# rs232_part.net
KiCad netlist of a schematic drawn in Altium Designer
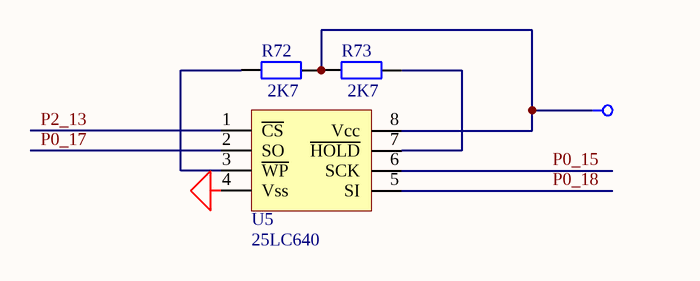
[diagram p0: rs232_part.SchDoc]

(export (version "E")
  (design (tool "Eeschema 10.0.6"))
  (components
    (comp (ref "R72")
      (value "2K7")
      (footprint "_1206")
      (description "Resistor")
      (fields (field (name "MANUFACTURER") "Generic Components") (field (name "PUBLISHER") "Altium Limited"))
      (libsource (lib "Miscellaneous Devices") (part "Res2"))
    )
    (comp (ref "R73")
      (value "2K7")
      (footprint "_1206")
      (description "Resistor")
      (fields (field (name "MANUFACTURER") "Generic Components") (field (name "PUBLISHER") "Altium Limited"))
      (libsource (lib "Miscellaneous Devices") (part "Res2"))
    )
    (comp (ref "U5") (value "25LC640") (footprint "SO-G8/D5") (libsource (lib "PAL") (part "25LC640")))
  )
  (nets
    (net (code "1") (name "+5v") (class "Default")
      (node (ref "R72") (pin "2") (pinfunction "2_2") (pintype "passive"))
      (node (ref "R73") (pin "1") (pinfunction "1_1") (pintype "passive"))
      (node (ref "U5") (pin "8") (pinfunction "Vcc_8") (pintype "passive"))
    )
    (net (code "2") (name "/P0_15") (class "Default")
      (node (ref "U5") (pin "6") (pinfunction "SCK_6") (pintype "passive"))
    )
    (net (code "3") (name "/P0_17") (class "Default")
      (node (ref "U5") (pin "2") (pinfunction "SO_2") (pintype "passive"))
    )
    (net (code "4") (name "/P0_18") (class "Default")
      (node (ref "U5") (pin "5") (pinfunction "SI_5") (pintype "passive"))
    )
    (net (code "5") (name "/P2_13") (class "Default")
      (node (ref "U5") (pin "1") (pinfunction "~{CS}_1") (pintype "passive"))
    )
    (net (code "6") (name "GND") (class "Default")
      (node (ref "U5") (pin "4") (pinfunction "Vss_4") (pintype "passive"))
    )
    (net (code "7") (name "Net-(U5-~{HOLD})") (class "Default")
      (node (ref "R73") (pin "2") (pinfunction "2_2") (pintype "passive"))
      (node (ref "U5") (pin "7") (pinfunction "~{HOLD}_7") (pintype "passive"))
    )
    (net (code "8") (name "Net-(U5-~{WP})") (class "Default")
      (node (ref "R72") (pin "1") (pinfunction "1_1") (pintype "passive"))
      (node (ref "U5") (pin "3") (pinfunction "~{WP}_3") (pintype "passive"))
    )
  )
)
